# Simple_Heart_v2_-_spider.net
KiCad netlist of a schematic drawn in EAGLE
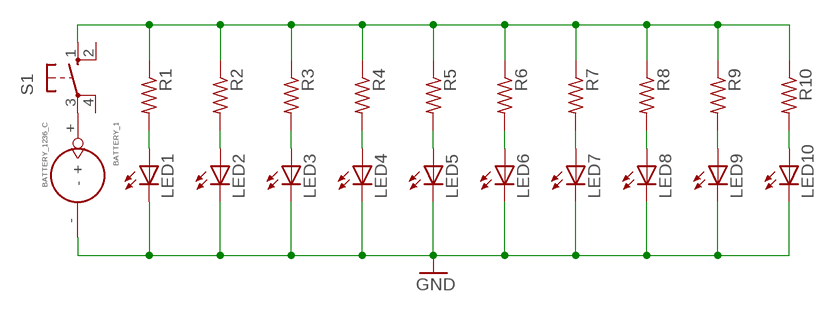
[diagram p0: schematic, sheet 1]

(export (version "E")
  (design (tool "Eeschema 10.0.6"))
  (components
    (comp (ref "BATTERY_1")
      (value "BATTERY_1236_C")
      (footprint "eagle-import:BATTERY_1236_C")
      (libsource (lib "eagle-import") (part "BATTERY_1236_C"))
    )
    (comp (ref "LED1")
      (value "LED5MM")
      (footprint "eagle-import:LED5MM")
      (libsource (lib "eagle-import") (part "LED5MM"))
    )
    (comp (ref "LED2")
      (value "LED5MM")
      (footprint "eagle-import:LED5MM")
      (libsource (lib "eagle-import") (part "LED5MM"))
    )
    (comp (ref "LED3")
      (value "LED5MM")
      (footprint "eagle-import:LED5MM")
      (libsource (lib "eagle-import") (part "LED5MM"))
    )
    (comp (ref "LED4")
      (value "LED5MM")
      (footprint "eagle-import:LED5MM")
      (libsource (lib "eagle-import") (part "LED5MM"))
    )
    (comp (ref "LED5")
      (value "LED5MM")
      (footprint "eagle-import:LED5MM")
      (libsource (lib "eagle-import") (part "LED5MM"))
    )
    (comp (ref "LED6")
      (value "LED5MM")
      (footprint "eagle-import:LED5MM")
      (libsource (lib "eagle-import") (part "LED5MM"))
    )
    (comp (ref "LED7")
      (value "LED5MM")
      (footprint "eagle-import:LED5MM")
      (libsource (lib "eagle-import") (part "LED5MM"))
    )
    (comp (ref "LED8")
      (value "LED5MM")
      (footprint "eagle-import:LED5MM")
      (libsource (lib "eagle-import") (part "LED5MM"))
    )
    (comp (ref "LED9")
      (value "LED5MM")
      (footprint "eagle-import:LED5MM")
      (libsource (lib "eagle-import") (part "LED5MM"))
    )
    (comp (ref "LED10")
      (value "LED5MM")
      (footprint "eagle-import:LED5MM")
      (libsource (lib "eagle-import") (part "LED5MM"))
    )
    (comp (ref "R1")
      (value "R-US_0204/7")
      (footprint "eagle-import:0204_7")
      (libsource (lib "eagle-import") (part "R-US_0204/7"))
    )
    (comp (ref "R2")
      (value "R-US_0204/7")
      (footprint "eagle-import:0204_7")
      (libsource (lib "eagle-import") (part "R-US_0204/7"))
    )
    (comp (ref "R3")
      (value "R-US_0204/7")
      (footprint "eagle-import:0204_7")
      (libsource (lib "eagle-import") (part "R-US_0204/7"))
    )
    (comp (ref "R4")
      (value "R-US_0204/7")
      (footprint "eagle-import:0204_7")
      (libsource (lib "eagle-import") (part "R-US_0204/7"))
    )
    (comp (ref "R5")
      (value "R-US_0204/7")
      (footprint "eagle-import:0204_7")
      (libsource (lib "eagle-import") (part "R-US_0204/7"))
    )
    (comp (ref "R6")
      (value "R-US_0204/7")
      (footprint "eagle-import:0204_7")
      (libsource (lib "eagle-import") (part "R-US_0204/7"))
    )
    (comp (ref "R7")
      (value "R-US_0204/7")
      (footprint "eagle-import:0204_7")
      (libsource (lib "eagle-import") (part "R-US_0204/7"))
    )
    (comp (ref "R8")
      (value "R-US_0204/7")
      (footprint "eagle-import:0204_7")
      (libsource (lib "eagle-import") (part "R-US_0204/7"))
    )
    (comp (ref "R9")
      (value "R-US_0204/7")
      (footprint "eagle-import:0204_7")
      (libsource (lib "eagle-import") (part "R-US_0204/7"))
    )
    (comp (ref "R10")
      (value "R-US_0204/7")
      (footprint "eagle-import:0204_7")
      (libsource (lib "eagle-import") (part "R-US_0204/7"))
    )
    (comp (ref "S1")
      (value "10-XX")
      (footprint "eagle-import:B3F-10XX")
      (fields (field (name "MPN") "B3F-1000"))
      (libsource (lib "eagle-import") (part "10-XX"))
    )
  )
  (nets
    (net (code "1") (name "GND") (class "Default")
      (node (ref "BATTERY_1") (pin "-") (pinfunction "-_-") (pintype "bidirectional"))
      (node (ref "LED1") (pin "K") (pinfunction "C_K") (pintype "passive"))
      (node (ref "LED10") (pin "K") (pinfunction "C_K") (pintype "passive"))
      (node (ref "LED2") (pin "K") (pinfunction "C_K") (pintype "passive"))
      (node (ref "LED3") (pin "K") (pinfunction "C_K") (pintype "passive"))
      (node (ref "LED4") (pin "K") (pinfunction "C_K") (pintype "passive"))
      (node (ref "LED5") (pin "K") (pinfunction "C_K") (pintype "passive"))
      (node (ref "LED6") (pin "K") (pinfunction "C_K") (pintype "passive"))
      (node (ref "LED7") (pin "K") (pinfunction "C_K") (pintype "passive"))
      (node (ref "LED8") (pin "K") (pinfunction "C_K") (pintype "passive"))
      (node (ref "LED9") (pin "K") (pinfunction "C_K") (pintype "passive"))
    )
    (net (code "2") (name "Net-(LED1-PadA)") (class "Default")
      (node (ref "LED1") (pin "A") (pinfunction "A_A") (pintype "passive"))
      (node (ref "R1") (pin "2") (pinfunction "2_2") (pintype "passive"))
    )
    (net (code "3") (name "Net-(LED2-PadA)") (class "Default")
      (node (ref "LED2") (pin "A") (pinfunction "A_A") (pintype "passive"))
      (node (ref "R2") (pin "2") (pinfunction "2_2") (pintype "passive"))
    )
    (net (code "4") (name "Net-(LED3-PadA)") (class "Default")
      (node (ref "LED3") (pin "A") (pinfunction "A_A") (pintype "passive"))
      (node (ref "R3") (pin "2") (pinfunction "2_2") (pintype "passive"))
    )
    (net (code "5") (name "Net-(LED4-PadA)") (class "Default")
      (node (ref "LED4") (pin "A") (pinfunction "A_A") (pintype "passive"))
      (node (ref "R4") (pin "2") (pinfunction "2_2") (pintype "passive"))
    )
    (net (code "6") (name "Net-(LED5-PadA)") (class "Default")
      (node (ref "LED5") (pin "A") (pinfunction "A_A") (pintype "passive"))
      (node (ref "R5") (pin "2") (pinfunction "2_2") (pintype "passive"))
    )
    (net (code "7") (name "Net-(LED6-PadA)") (class "Default")
      (node (ref "LED6") (pin "A") (pinfunction "A_A") (pintype "passive"))
      (node (ref "R6") (pin "2") (pinfunction "2_2") (pintype "passive"))
    )
    (net (code "8") (name "Net-(LED7-PadA)") (class "Default")
      (node (ref "LED7") (pin "A") (pinfunction "A_A") (pintype "passive"))
      (node (ref "R7") (pin "2") (pinfunction "2_2") (pintype "passive"))
    )
    (net (code "9") (name "Net-(LED8-PadA)") (class "Default")
      (node (ref "LED8") (pin "A") (pinfunction "A_A") (pintype "passive"))
      (node (ref "R8") (pin "2") (pinfunction "2_2") (pintype "passive"))
    )
    (net (code "10") (name "Net-(LED9-PadA)") (class "Default")
      (node (ref "LED9") (pin "A") (pinfunction "A_A") (pintype "passive"))
      (node (ref "R9") (pin "2") (pinfunction "2_2") (pintype "passive"))
    )
    (net (code "11") (name "Net-(LED10-PadA)") (class "Default")
      (node (ref "LED10") (pin "A") (pinfunction "A_A") (pintype "passive"))
      (node (ref "R10") (pin "2") (pinfunction "2_2") (pintype "passive"))
    )
    (net (code "12") (name "Net-(S1-P)") (class "Default")
      (node (ref "BATTERY_1") (pin "+") (pinfunction "+_+") (pintype "bidirectional"))
      (node (ref "S1") (pin "3") (pinfunction "P_3") (pintype "passive"))
    )
    (net (code "13") (name "Net-(S1-S)") (class "Default")
      (node (ref "R1") (pin "1") (pinfunction "1_1") (pintype "passive"))
      (node (ref "R10") (pin "1") (pinfunction "1_1") (pintype "passive"))
      (node (ref "R2") (pin "1") (pinfunction "1_1") (pintype "passive"))
      (node (ref "R3") (pin "1") (pinfunction "1_1") (pintype "passive"))
      (node (ref "R4") (pin "1") (pinfunction "1_1") (pintype "passive"))
      (node (ref "R5") (pin "1") (pinfunction "1_1") (pintype "passive"))
      (node (ref "R6") (pin "1") (pinfunction "1_1") (pintype "passive"))
      (node (ref "R7") (pin "1") (pinfunction "1_1") (pintype "passive"))
      (node (ref "R8") (pin "1") (pinfunction "1_1") (pintype "passive"))
      (node (ref "R9") (pin "1") (pinfunction "1_1") (pintype "passive"))
      (node (ref "S1") (pin "1") (pinfunction "S_1") (pintype "passive"))
    )
    (net (code "14") (name "unconnected-(S1-P1-Pad4)") (class "Default")
      (node (ref "S1") (pin "4") (pinfunction "P1_4") (pintype "passive"))
    )
    (net (code "15") (name "unconnected-(S1-S1-Pad2)") (class "Default")
      (node (ref "S1") (pin "2") (pinfunction "S1_2") (pintype "passive"))
    )
  )
)
